# DroidCONuino_v1_2.net
KiCad netlist of a schematic drawn in EAGLE
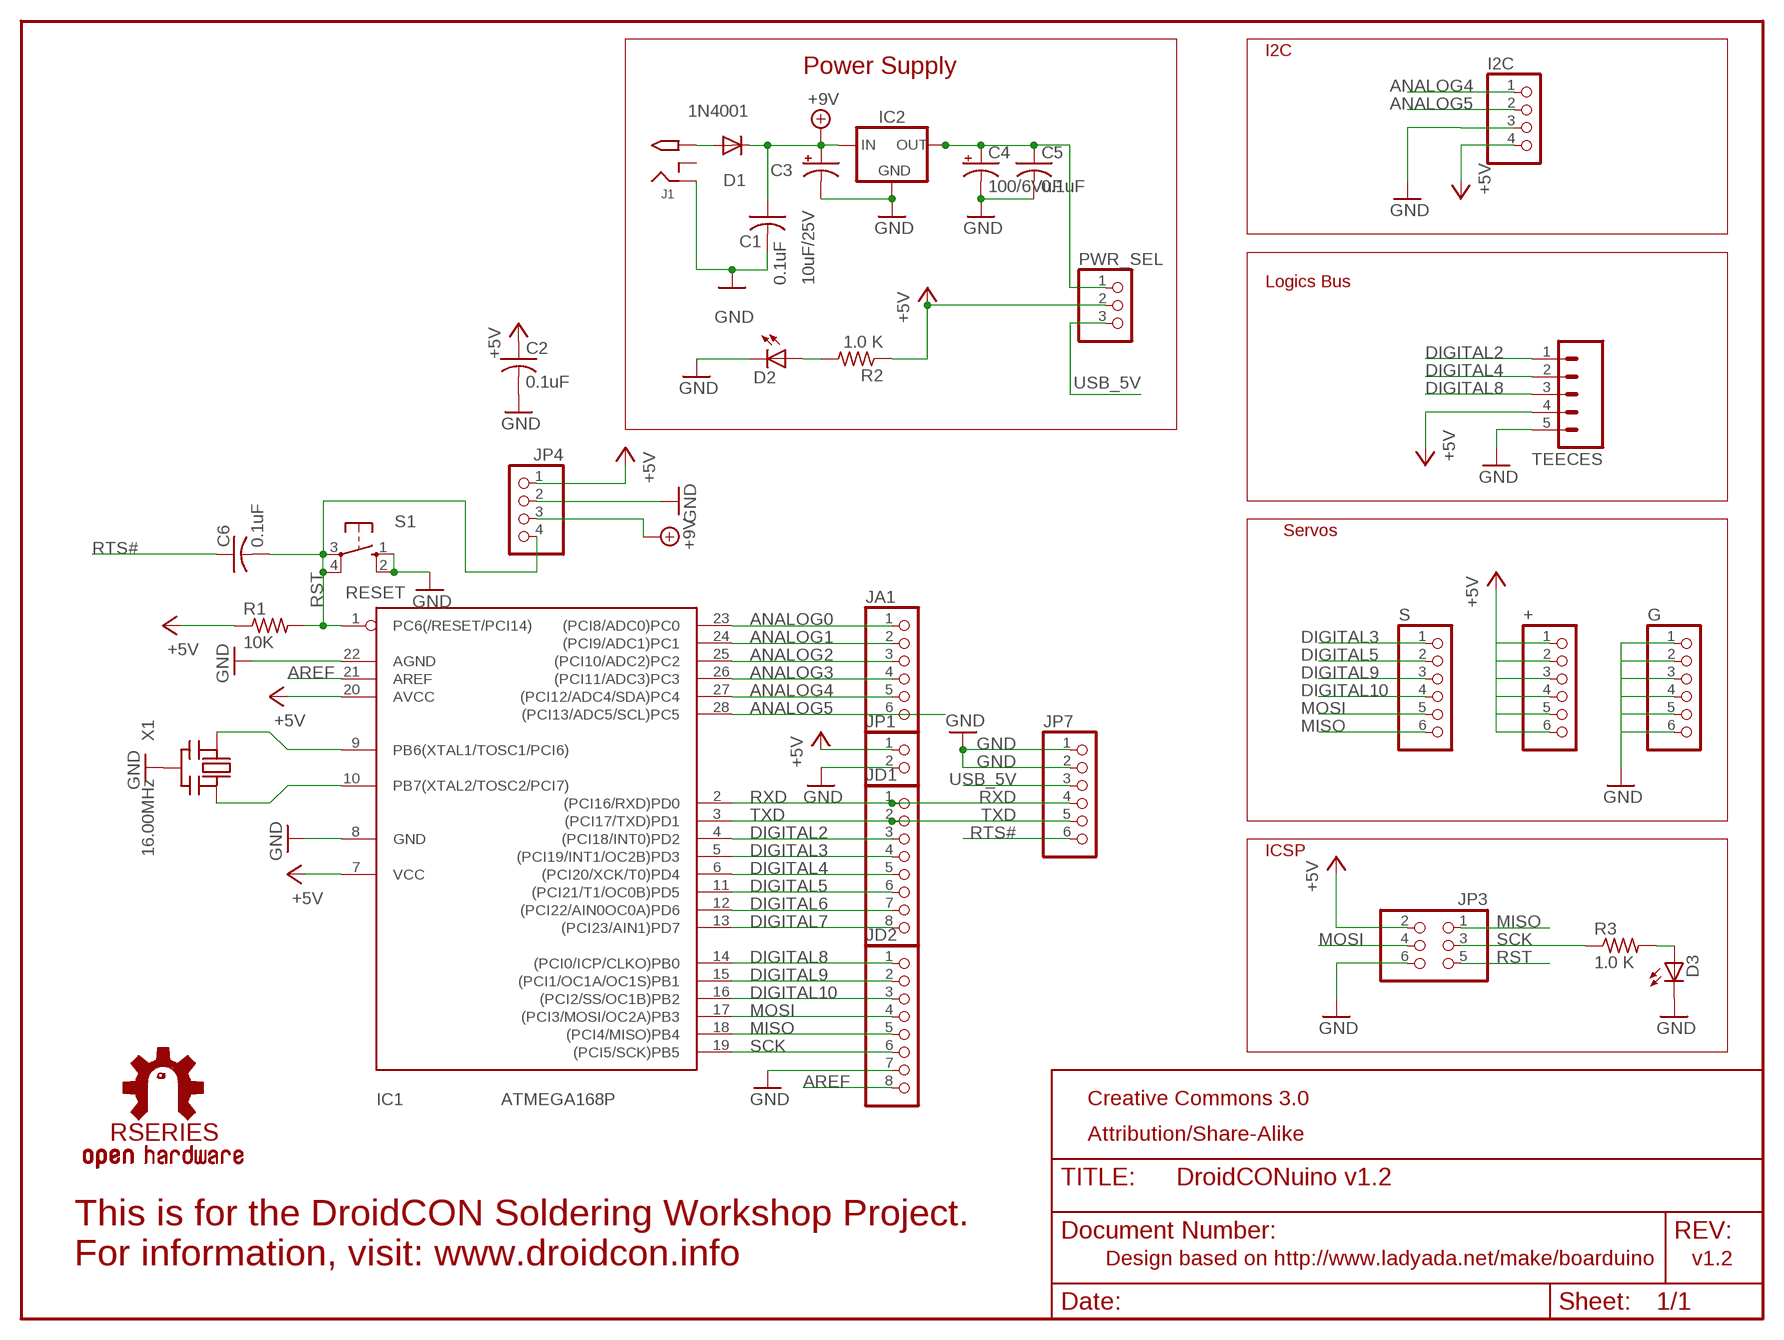
[diagram p0: schematic, sheet 1]

(export (version "E")
  (design (tool "Eeschema 10.0.6"))
  (components
    (comp (ref "+")
      (value "PINHD-1X6CLEAN")
      (footprint "eagle-import:1X06-CLEAN")
      (libsource (lib "eagle-import") (part "PINHD-1X6CLEAN"))
    )
    (comp (ref "C1")
      (value "0.1uF")
      (footprint "eagle-import:C025-025X050")
      (libsource (lib "eagle-import") (part "C-US025-025X050"))
    )
    (comp (ref "C2")
      (value "0.1uF")
      (footprint "eagle-import:C025-025X050")
      (libsource (lib "eagle-import") (part "C-US025-025X050"))
    )
    (comp (ref "C3")
      (value "10uF/25V")
      (footprint "eagle-import:E2,5-6")
      (libsource (lib "eagle-import") (part "CPOL-USE2.5-6"))
    )
    (comp (ref "C4")
      (value "100/6VuF")
      (footprint "eagle-import:E2,5-6")
      (libsource (lib "eagle-import") (part "CPOL-USE2.5-6"))
    )
    (comp (ref "C5")
      (value "0.1uF")
      (footprint "eagle-import:C025-025X050")
      (libsource (lib "eagle-import") (part "C-US025-025X050"))
    )
    (comp (ref "C6")
      (value "0.1uF")
      (footprint "eagle-import:C025-025X050")
      (libsource (lib "eagle-import") (part "C-US025-025X050"))
    )
    (comp (ref "D1")
      (value "1N4001")
      (footprint "eagle-import:DO41-10")
      (libsource (lib "eagle-import") (part "1N4004"))
    )
    (comp (ref "D2")
      (value "LED3MM")
      (footprint "eagle-import:LED3MM")
      (libsource (lib "eagle-import") (part "LED3MM"))
    )
    (comp (ref "D3")
      (value "Green")
      (footprint "eagle-import:LED3MM")
      (libsource (lib "eagle-import") (part "LED3MM"))
    )
    (comp (ref "G")
      (value "PINHD-1X6CLEAN")
      (footprint "eagle-import:1X06-CLEAN")
      (libsource (lib "eagle-import") (part "PINHD-1X6CLEAN"))
    )
    (comp (ref "I2C")
      (value "PINHD-1X4CB")
      (footprint "eagle-import:1X04-CB")
      (libsource (lib "eagle-import") (part "PINHD-1X4CB"))
    )
    (comp (ref "IC1")
      (value "ATMEGA168P")
      (footprint "eagle-import:DIL28_3")
      (libsource (lib "eagle-import") (part "ATMEGA168PROUND"))
    )
    (comp (ref "IC2")
      (value "78XXS")
      (footprint "eagle-import:78XXS")
      (libsource (lib "eagle-import") (part "78XXS"))
    )
    (comp (ref "J1")
      (value "2.1MMJACK")
      (footprint "eagle-import:PJ-102A")
      (libsource (lib "eagle-import") (part "2.1MMJACK"))
    )
    (comp (ref "JA1")
      (value "PINHD-1X6CB")
      (footprint "eagle-import:1X06-CLEANBIG")
      (libsource (lib "eagle-import") (part "PINHD-1X6CB"))
    )
    (comp (ref "JD1")
      (value "PINHD-1X8CLEANBIG")
      (footprint "eagle-import:1X08-CLEANBIG")
      (libsource (lib "eagle-import") (part "PINHD-1X8CLEANBIG"))
    )
    (comp (ref "JD2")
      (value "PINHD-1X8CLEANBIG")
      (footprint "eagle-import:1X08-CLEANBIG")
      (libsource (lib "eagle-import") (part "PINHD-1X8CLEANBIG"))
    )
    (comp (ref "JP1")
      (value "PINHD-1X2CB")
      (footprint "eagle-import:1X02-CB")
      (libsource (lib "eagle-import") (part "PINHD-1X2CB"))
    )
    (comp (ref "JP3")
      (value "PINHD-2X3")
      (footprint "eagle-import:2X03")
      (libsource (lib "eagle-import") (part "PINHD-2X3"))
    )
    (comp (ref "JP4")
      (value "PINHD-1X4CB")
      (footprint "eagle-import:1X04-CB")
      (libsource (lib "eagle-import") (part "PINHD-1X4CB"))
    )
    (comp (ref "JP7")
      (value "PINHD-1X6CLEAN")
      (footprint "eagle-import:1X06-CLEAN")
      (libsource (lib "eagle-import") (part "PINHD-1X6CLEAN"))
    )
    (comp (ref "PWR_SEL")
      (value "PINHD-1X3")
      (footprint "eagle-import:1X03")
      (libsource (lib "eagle-import") (part "PINHD-1X3"))
    )
    (comp (ref "R1")
      (value "10K")
      (footprint "eagle-import:0207_5V")
      (libsource (lib "eagle-import") (part "rcl-ez_R-US_0207/5V"))
    )
    (comp (ref "R2")
      (value "1.0 K")
      (footprint "eagle-import:0207_5V")
      (libsource (lib "eagle-import") (part "R-US_0207/5V"))
    )
    (comp (ref "R3")
      (value "1.0 K")
      (footprint "eagle-import:0207_5V")
      (libsource (lib "eagle-import") (part "R-US_0207/5V"))
    )
    (comp (ref "S")
      (value "PINHD-1X6CLEAN")
      (footprint "eagle-import:1X06-CLEAN")
      (libsource (lib "eagle-import") (part "PINHD-1X6CLEAN"))
    )
    (comp (ref "S1")
      (value "RESET")
      (footprint "eagle-import:B3F-10XX")
      (libsource (lib "eagle-import") (part "10-XX"))
    )
    (comp (ref "TEECES")
      (value "M05PTH")
      (footprint "eagle-import:1X05")
      (libsource (lib "eagle-import") (part "M05PTH"))
    )
    (comp (ref "U$2")
      (value "RSERIES-OSHW-LOGOMEDIUM")
      (footprint "eagle-import:RSERIES-OSHW-LOGO-MEDIUM")
      (libsource (lib "eagle-import") (part "RSERIES-OSHW-LOGOMEDIUM"))
    )
    (comp (ref "X1")
      (value "16.00MHz")
      (footprint "eagle-import:CERM_OSC")
      (libsource (lib "eagle-import") (part "CERMOSCILL"))
    )
  )
  (nets
    (net (code "1") (name "+5V") (class "Default")
      (node (ref "+") (pin "1") (pinfunction "1_1") (pintype "passive"))
      (node (ref "+") (pin "2") (pinfunction "2_2") (pintype "passive"))
      (node (ref "+") (pin "3") (pinfunction "3_3") (pintype "passive"))
      (node (ref "+") (pin "4") (pinfunction "4_4") (pintype "passive"))
      (node (ref "+") (pin "5") (pinfunction "5_5") (pintype "passive"))
      (node (ref "+") (pin "6") (pinfunction "6_6") (pintype "passive"))
      (node (ref "C2") (pin "1") (pinfunction "1_1") (pintype "passive"))
      (node (ref "I2C") (pin "4") (pinfunction "4_4") (pintype "passive"))
      (node (ref "IC1") (pin "20") (pinfunction "AVCC_20") (pintype "bidirectional"))
      (node (ref "IC1") (pin "7") (pinfunction "VCC_7") (pintype "bidirectional"))
      (node (ref "JP1") (pin "1") (pinfunction "1_1") (pintype "passive"))
      (node (ref "JP3") (pin "2") (pinfunction "2_2") (pintype "passive"))
      (node (ref "JP4") (pin "1") (pinfunction "1_1") (pintype "passive"))
      (node (ref "PWR_SEL") (pin "2") (pinfunction "2_2") (pintype "passive"))
      (node (ref "R1") (pin "1") (pinfunction "1_1") (pintype "passive"))
      (node (ref "R2") (pin "1") (pinfunction "1_1") (pintype "passive"))
      (node (ref "TEECES") (pin "4") (pinfunction "4_4") (pintype "passive"))
    )
    (net (code "2") (name "+9V") (class "Default")
      (node (ref "C1") (pin "1") (pinfunction "1_1") (pintype "passive"))
      (node (ref "C3") (pin "+") (pinfunction "+_+") (pintype "passive"))
      (node (ref "D1") (pin "C") (pinfunction "C_C") (pintype "passive"))
      (node (ref "IC2") (pin "IN") (pinfunction "IN_IN") (pintype "input"))
      (node (ref "JP4") (pin "3") (pinfunction "3_3") (pintype "passive"))
    )
    (net (code "3") (name "/ANALOG0") (class "Default")
      (node (ref "IC1") (pin "23") (pinfunction "(PCI8/ADC0)PC0_23") (pintype "bidirectional"))
      (node (ref "JA1") (pin "1") (pinfunction "1_1") (pintype "passive"))
    )
    (net (code "4") (name "/ANALOG1") (class "Default")
      (node (ref "IC1") (pin "24") (pinfunction "(PCI9/ADC1)PC1_24") (pintype "bidirectional"))
      (node (ref "JA1") (pin "2") (pinfunction "2_2") (pintype "passive"))
    )
    (net (code "5") (name "/ANALOG2") (class "Default")
      (node (ref "IC1") (pin "25") (pinfunction "(PCI10/ADC2)PC2_25") (pintype "bidirectional"))
      (node (ref "JA1") (pin "3") (pinfunction "3_3") (pintype "passive"))
    )
    (net (code "6") (name "/ANALOG3") (class "Default")
      (node (ref "IC1") (pin "26") (pinfunction "(PCI11/ADC3)PC3_26") (pintype "bidirectional"))
      (node (ref "JA1") (pin "4") (pinfunction "4_4") (pintype "passive"))
    )
    (net (code "7") (name "/ANALOG4") (class "Default")
      (node (ref "I2C") (pin "1") (pinfunction "1_1") (pintype "passive"))
      (node (ref "IC1") (pin "27") (pinfunction "(PCI12/ADC4/SDA)PC4_27") (pintype "bidirectional"))
      (node (ref "JA1") (pin "5") (pinfunction "5_5") (pintype "passive"))
    )
    (net (code "8") (name "/ANALOG5") (class "Default")
      (node (ref "I2C") (pin "2") (pinfunction "2_2") (pintype "passive"))
      (node (ref "IC1") (pin "28") (pinfunction "(PCI13/ADC5/SCL)PC5_28") (pintype "bidirectional"))
      (node (ref "JA1") (pin "6") (pinfunction "6_6") (pintype "passive"))
    )
    (net (code "9") (name "/AREF") (class "Default")
      (node (ref "IC1") (pin "21") (pinfunction "AREF_21") (pintype "bidirectional"))
      (node (ref "JD2") (pin "8") (pinfunction "8_8") (pintype "passive"))
    )
    (net (code "10") (name "/DIGITAL2") (class "Default")
      (node (ref "IC1") (pin "4") (pinfunction "(PCI18/INT0)PD2_4") (pintype "bidirectional"))
      (node (ref "JD1") (pin "3") (pinfunction "3_3") (pintype "passive"))
      (node (ref "TEECES") (pin "1") (pinfunction "1_1") (pintype "passive"))
    )
    (net (code "11") (name "/DIGITAL3") (class "Default")
      (node (ref "IC1") (pin "5") (pinfunction "(PCI19/INT1/OC2B)PD3_5") (pintype "bidirectional"))
      (node (ref "JD1") (pin "4") (pinfunction "4_4") (pintype "passive"))
      (node (ref "S") (pin "1") (pinfunction "1_1") (pintype "passive"))
    )
    (net (code "12") (name "/DIGITAL4") (class "Default")
      (node (ref "IC1") (pin "6") (pinfunction "(PCI20/XCK/T0)PD4_6") (pintype "bidirectional"))
      (node (ref "JD1") (pin "5") (pinfunction "5_5") (pintype "passive"))
      (node (ref "TEECES") (pin "2") (pinfunction "2_2") (pintype "passive"))
    )
    (net (code "13") (name "/DIGITAL5") (class "Default")
      (node (ref "IC1") (pin "11") (pinfunction "(PCI21/T1/OC0B)PD5_11") (pintype "bidirectional"))
      (node (ref "JD1") (pin "6") (pinfunction "6_6") (pintype "passive"))
      (node (ref "S") (pin "2") (pinfunction "2_2") (pintype "passive"))
    )
    (net (code "14") (name "/DIGITAL6") (class "Default")
      (node (ref "IC1") (pin "12") (pinfunction "(PCI22/AIN0OC0A)PD6_12") (pintype "bidirectional"))
      (node (ref "JD1") (pin "7") (pinfunction "7_7") (pintype "passive"))
    )
    (net (code "15") (name "/DIGITAL7") (class "Default")
      (node (ref "IC1") (pin "13") (pinfunction "(PCI23/AIN1)PD7_13") (pintype "bidirectional"))
      (node (ref "JD1") (pin "8") (pinfunction "8_8") (pintype "passive"))
    )
    (net (code "16") (name "/DIGITAL8") (class "Default")
      (node (ref "IC1") (pin "14") (pinfunction "(PCI0/ICP/CLKO)PB0_14") (pintype "bidirectional"))
      (node (ref "JD2") (pin "1") (pinfunction "1_1") (pintype "passive"))
      (node (ref "TEECES") (pin "3") (pinfunction "3_3") (pintype "passive"))
    )
    (net (code "17") (name "/DIGITAL9") (class "Default")
      (node (ref "IC1") (pin "15") (pinfunction "(PCI1/OC1A/OC1S)PB1_15") (pintype "bidirectional"))
      (node (ref "JD2") (pin "2") (pinfunction "2_2") (pintype "passive"))
      (node (ref "S") (pin "3") (pinfunction "3_3") (pintype "passive"))
    )
    (net (code "18") (name "/DIGITAL10") (class "Default")
      (node (ref "IC1") (pin "16") (pinfunction "(PCI2/SS/OC1B)PB2_16") (pintype "bidirectional"))
      (node (ref "JD2") (pin "3") (pinfunction "3_3") (pintype "passive"))
      (node (ref "S") (pin "4") (pinfunction "4_4") (pintype "passive"))
    )
    (net (code "19") (name "/MISO") (class "Default")
      (node (ref "IC1") (pin "18") (pinfunction "(PCI4/MISO)PB4_18") (pintype "bidirectional"))
      (node (ref "JD2") (pin "5") (pinfunction "5_5") (pintype "passive"))
      (node (ref "JP3") (pin "1") (pinfunction "1_1") (pintype "passive"))
      (node (ref "S") (pin "6") (pinfunction "6_6") (pintype "passive"))
    )
    (net (code "20") (name "/MOSI") (class "Default")
      (node (ref "IC1") (pin "17") (pinfunction "(PCI3/MOSI/OC2A)PB3_17") (pintype "bidirectional"))
      (node (ref "JD2") (pin "4") (pinfunction "4_4") (pintype "passive"))
      (node (ref "JP3") (pin "4") (pinfunction "4_4") (pintype "passive"))
      (node (ref "S") (pin "5") (pinfunction "5_5") (pintype "passive"))
    )
    (net (code "21") (name "/RST") (class "Default")
      (node (ref "C6") (pin "2") (pinfunction "2_2") (pintype "passive"))
      (node (ref "IC1") (pin "1") (pinfunction "PC6(/RESET/PCI14)_1") (pintype "bidirectional"))
      (node (ref "JP3") (pin "5") (pinfunction "5_5") (pintype "passive"))
      (node (ref "JP4") (pin "4") (pinfunction "4_4") (pintype "passive"))
      (node (ref "R1") (pin "2") (pinfunction "2_2") (pintype "passive"))
      (node (ref "S1") (pin "3") (pinfunction "P_3") (pintype "passive"))
      (node (ref "S1") (pin "4") (pinfunction "P1_4") (pintype "passive"))
    )
    (net (code "22") (name "/RTS#") (class "Default")
      (node (ref "C6") (pin "1") (pinfunction "1_1") (pintype "passive"))
      (node (ref "JP7") (pin "6") (pinfunction "6_6") (pintype "passive"))
    )
    (net (code "23") (name "/RXD") (class "Default")
      (node (ref "IC1") (pin "2") (pinfunction "(PCI16/RXD)PD0_2") (pintype "bidirectional"))
      (node (ref "JD1") (pin "1") (pinfunction "1_1") (pintype "passive"))
      (node (ref "JP7") (pin "4") (pinfunction "4_4") (pintype "passive"))
    )
    (net (code "24") (name "/SCK") (class "Default")
      (node (ref "IC1") (pin "19") (pinfunction "(PCI5/SCK)PB5_19") (pintype "bidirectional"))
      (node (ref "JD2") (pin "6") (pinfunction "6_6") (pintype "passive"))
      (node (ref "JP3") (pin "3") (pinfunction "3_3") (pintype "passive"))
      (node (ref "R3") (pin "1") (pinfunction "1_1") (pintype "passive"))
    )
    (net (code "25") (name "/TXD") (class "Default")
      (node (ref "IC1") (pin "3") (pinfunction "(PCI17/TXD)PD1_3") (pintype "bidirectional"))
      (node (ref "JD1") (pin "2") (pinfunction "2_2") (pintype "passive"))
      (node (ref "JP7") (pin "5") (pinfunction "5_5") (pintype "passive"))
    )
    (net (code "26") (name "/USB_5V") (class "Default")
      (node (ref "JP7") (pin "3") (pinfunction "3_3") (pintype "passive"))
      (node (ref "PWR_SEL") (pin "3") (pinfunction "3_3") (pintype "passive"))
    )
    (net (code "27") (name "GND") (class "Default")
      (node (ref "C1") (pin "2") (pinfunction "2_2") (pintype "passive"))
      (node (ref "C2") (pin "2") (pinfunction "2_2") (pintype "passive"))
      (node (ref "C3") (pin "-") (pinfunction "-_-") (pintype "passive"))
      (node (ref "C4") (pin "-") (pinfunction "-_-") (pintype "passive"))
      (node (ref "C5") (pin "2") (pinfunction "2_2") (pintype "passive"))
      (node (ref "D2") (pin "K") (pinfunction "C_K") (pintype "passive"))
      (node (ref "D3") (pin "K") (pinfunction "C_K") (pintype "passive"))
      (node (ref "G") (pin "1") (pinfunction "1_1") (pintype "passive"))
      (node (ref "G") (pin "2") (pinfunction "2_2") (pintype "passive"))
      (node (ref "G") (pin "3") (pinfunction "3_3") (pintype "passive"))
      (node (ref "G") (pin "4") (pinfunction "4_4") (pintype "passive"))
      (node (ref "G") (pin "5") (pinfunction "5_5") (pintype "passive"))
      (node (ref "G") (pin "6") (pinfunction "6_6") (pintype "passive"))
      (node (ref "I2C") (pin "3") (pinfunction "3_3") (pintype "passive"))
      (node (ref "IC1") (pin "22") (pinfunction "AGND_22") (pintype "bidirectional"))
      (node (ref "IC1") (pin "8") (pinfunction "GND_8") (pintype "bidirectional"))
      (node (ref "IC2") (pin "GND") (pinfunction "GND_GND") (pintype "input"))
      (node (ref "J1") (pin "RING") (pinfunction "RING_RING") (pintype "bidirectional"))
      (node (ref "JD2") (pin "7") (pinfunction "7_7") (pintype "passive"))
      (node (ref "JP1") (pin "2") (pinfunction "2_2") (pintype "passive"))
      (node (ref "JP3") (pin "6") (pinfunction "6_6") (pintype "passive"))
      (node (ref "JP4") (pin "2") (pinfunction "2_2") (pintype "passive"))
      (node (ref "JP7") (pin "1") (pinfunction "1_1") (pintype "passive"))
      (node (ref "JP7") (pin "2") (pinfunction "2_2") (pintype "passive"))
      (node (ref "S1") (pin "1") (pinfunction "S_1") (pintype "passive"))
      (node (ref "S1") (pin "2") (pinfunction "S1_2") (pintype "passive"))
      (node (ref "TEECES") (pin "5") (pinfunction "5_5") (pintype "passive"))
      (node (ref "X1") (pin "P$2") (pinfunction "GND_P$2") (pintype "bidirectional"))
    )
    (net (code "28") (name "Net-(C4-Pad+)") (class "Default")
      (node (ref "C4") (pin "+") (pinfunction "+_+") (pintype "passive"))
      (node (ref "C5") (pin "1") (pinfunction "1_1") (pintype "passive"))
      (node (ref "IC2") (pin "OUT") (pinfunction "OUT_OUT") (pintype "passive"))
      (node (ref "PWR_SEL") (pin "1") (pinfunction "1_1") (pintype "passive"))
    )
    (net (code "29") (name "Net-(D1-PadA)") (class "Default")
      (node (ref "D1") (pin "A") (pinfunction "A_A") (pintype "passive"))
      (node (ref "J1") (pin "TIP") (pinfunction "TIP_TIP") (pintype "bidirectional"))
    )
    (net (code "30") (name "Net-(D2-PadA)") (class "Default")
      (node (ref "D2") (pin "A") (pinfunction "A_A") (pintype "passive"))
      (node (ref "R2") (pin "2") (pinfunction "2_2") (pintype "passive"))
    )
    (net (code "31") (name "Net-(D3-PadA)") (class "Default")
      (node (ref "D3") (pin "A") (pinfunction "A_A") (pintype "passive"))
      (node (ref "R3") (pin "2") (pinfunction "2_2") (pintype "passive"))
    )
    (net (code "32") (name "Net-(IC1-PB6(XTAL1{slash}TOSC1{slash}PCI6))") (class "Default")
      (node (ref "IC1") (pin "9") (pinfunction "PB6(XTAL1/TOSC1/PCI6)_9") (pintype "bidirectional"))
      (node (ref "X1") (pin "P$1") (pinfunction "IN_P$1") (pintype "bidirectional"))
    )
    (net (code "33") (name "Net-(IC1-PB7(XTAL2{slash}TOSC2{slash}PCI7))") (class "Default")
      (node (ref "IC1") (pin "10") (pinfunction "PB7(XTAL2/TOSC2/PCI7)_10") (pintype "bidirectional"))
      (node (ref "X1") (pin "P$3") (pinfunction "OUT_P$3") (pintype "bidirectional"))
    )
    (net (code "34") (name "unconnected-(J1-PadRING_SW)") (class "Default")
      (node (ref "J1") (pin "RING_SW") (pinfunction "RING_SW_RING_SW") (pintype "bidirectional"))
    )
  )
)
